# PowerBoard_Rev1.net
KiCad netlist of a schematic drawn in Altium Designer
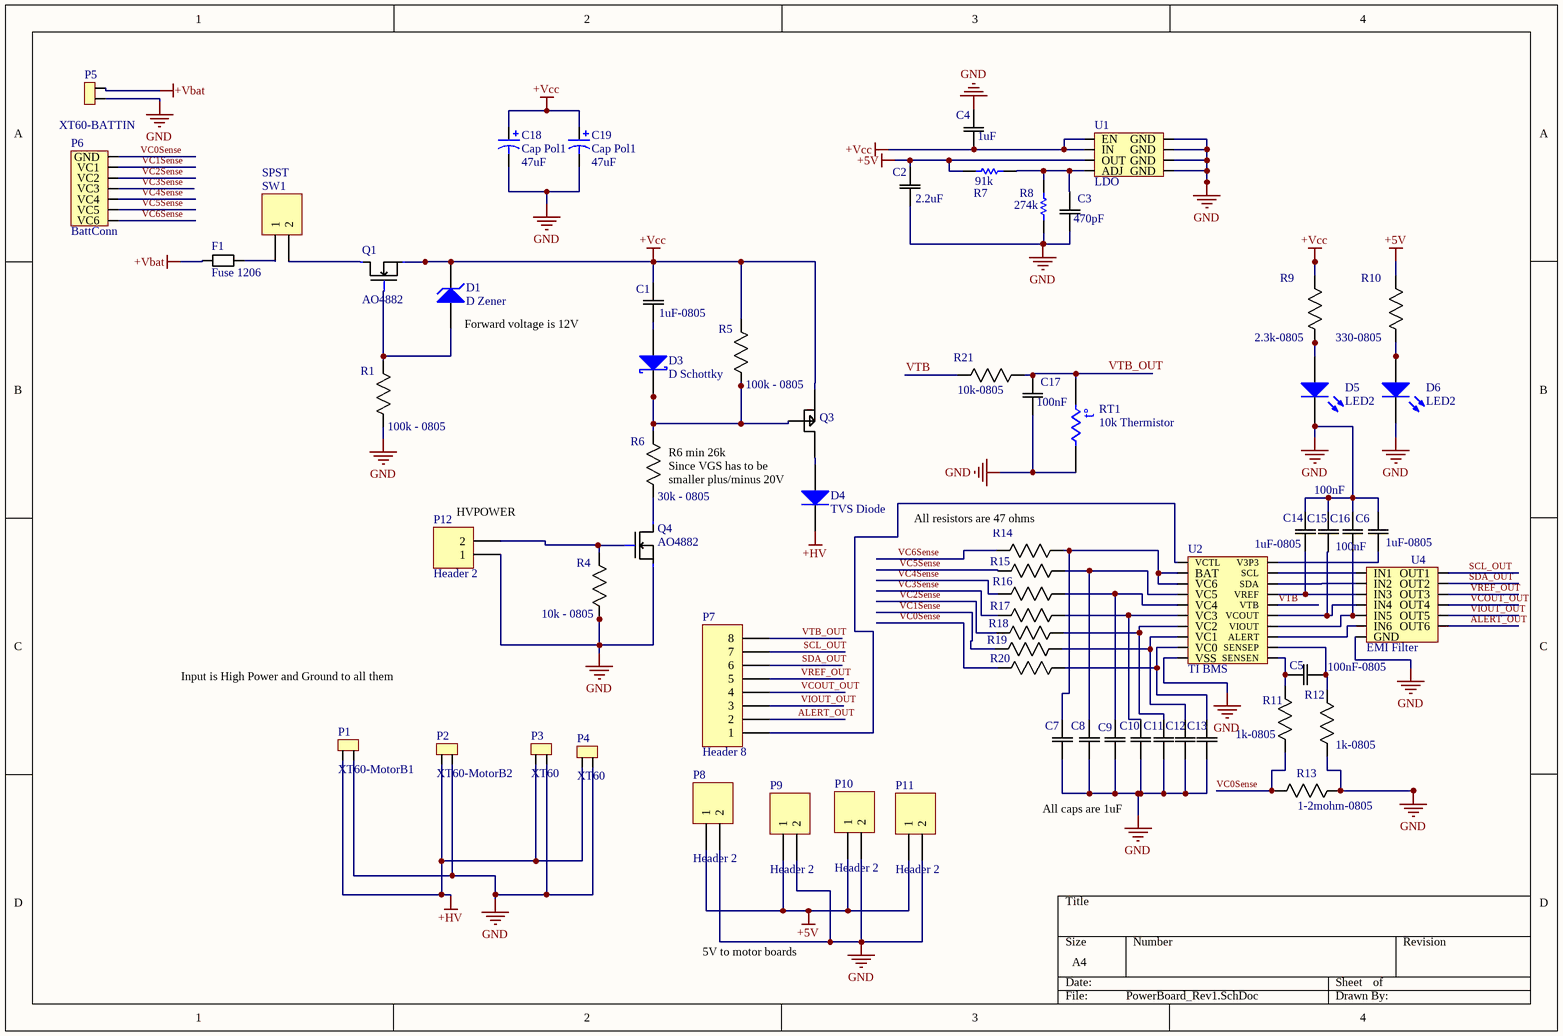
[diagram p0: PowerBoard_Rev1.SchDoc]

(export (version "E")
  (design (tool "Eeschema 10.0.6"))
  (components
    (comp (ref "C1")
      (value "1uF-0805")
      (footprint "CAPC2013X110N")
      (description "Capacitor; Ceramic; Cap; .100UF ; Tol+-10%; SMD; Vol-Rtg 50V; X7R, Tape/Reel")
      (fields (field (name "MP") "C0805C104K5RACTU") (field (name "MF") "Kemet"))
      (libsource (lib "100nF-C0805C104K5RACTU") (part "C0805C104K5RACTU"))
    )
    (comp (ref "C2")
      (value "2.2uF")
      (footprint "CAPC2013X110N")
      (description "Capacitor; Ceramic; Cap; .100UF ; Tol+-10%; SMD; Vol-Rtg 50V; X7R, Tape/Reel")
      (fields (field (name "MP") "C0805C104K5RACTU") (field (name "MF") "Kemet"))
      (libsource (lib "") (part "C0805C104K5RACTU_1"))
    )
    (comp (ref "C3")
      (value "470pF")
      (footprint "CAPC2013X110N")
      (description "Capacitor; Ceramic; Cap; .100UF ; Tol+-10%; SMD; Vol-Rtg 50V; X7R, Tape/Reel")
      (fields (field (name "MP") "C0805C104K5RACTU") (field (name "MF") "Kemet"))
      (libsource (lib "") (part "C0805C104K5RACTU_1"))
    )
    (comp (ref "C4")
      (value "1uF")
      (footprint "CAPC2013X110N")
      (description "Capacitor; Ceramic; Cap; .100UF ; Tol+-10%; SMD; Vol-Rtg 50V; X7R, Tape/Reel")
      (fields (field (name "MP") "C0805C104K5RACTU") (field (name "MF") "Kemet"))
      (libsource (lib "") (part "C0805C104K5RACTU_1"))
    )
    (comp (ref "C5")
      (value "100nF-0805")
      (footprint "CAPC2013X110N")
      (description "Capacitor; Ceramic; Cap; .100UF ; Tol+-10%; SMD; Vol-Rtg 50V; X7R, Tape/Reel")
      (fields (field (name "MP") "C0805C104K5RACTU") (field (name "MF") "Kemet"))
      (libsource (lib "100nF-C0805C104K5RACTU") (part "C0805C104K5RACTU"))
    )
    (comp (ref "C6")
      (value "1uF-0805")
      (footprint "CAPC2013X110N")
      (description "Capacitor; Ceramic; Cap; .100UF ; Tol+-10%; SMD; Vol-Rtg 50V; X7R, Tape/Reel")
      (fields (field (name "MP") "C0805C104K5RACTU") (field (name "MF") "Kemet"))
      (libsource (lib "100nF-C0805C104K5RACTU") (part "C0805C104K5RACTU"))
    )
    (comp (ref "C7")
      (value "1uF-0805")
      (footprint "CAPC2013X110N")
      (description "Capacitor; Ceramic; Cap; .100UF ; Tol+-10%; SMD; Vol-Rtg 50V; X7R, Tape/Reel")
      (fields (field (name "MP") "C0805C104K5RACTU") (field (name "MF") "Kemet"))
      (libsource (lib "100nF-C0805C104K5RACTU") (part "C0805C104K5RACTU"))
    )
    (comp (ref "C8")
      (value "1uF-0805")
      (footprint "CAPC2013X110N")
      (description "Capacitor; Ceramic; Cap; .100UF ; Tol+-10%; SMD; Vol-Rtg 50V; X7R, Tape/Reel")
      (fields (field (name "MP") "C0805C104K5RACTU") (field (name "MF") "Kemet"))
      (libsource (lib "100nF-C0805C104K5RACTU") (part "C0805C104K5RACTU"))
    )
    (comp (ref "C9")
      (value "1uF-0805")
      (footprint "CAPC2013X110N")
      (description "Capacitor; Ceramic; Cap; .100UF ; Tol+-10%; SMD; Vol-Rtg 50V; X7R, Tape/Reel")
      (fields (field (name "MP") "C0805C104K5RACTU") (field (name "MF") "Kemet"))
      (libsource (lib "100nF-C0805C104K5RACTU") (part "C0805C104K5RACTU"))
    )
    (comp (ref "C10")
      (value "1uF-0805")
      (footprint "CAPC2013X110N")
      (description "Capacitor; Ceramic; Cap; .100UF ; Tol+-10%; SMD; Vol-Rtg 50V; X7R, Tape/Reel")
      (fields (field (name "MP") "C0805C104K5RACTU") (field (name "MF") "Kemet"))
      (libsource (lib "100nF-C0805C104K5RACTU") (part "C0805C104K5RACTU"))
    )
    (comp (ref "C11")
      (value "1uF-0805")
      (footprint "CAPC2013X110N")
      (description "Capacitor; Ceramic; Cap; .100UF ; Tol+-10%; SMD; Vol-Rtg 50V; X7R, Tape/Reel")
      (fields (field (name "MP") "C0805C104K5RACTU") (field (name "MF") "Kemet"))
      (libsource (lib "100nF-C0805C104K5RACTU") (part "C0805C104K5RACTU"))
    )
    (comp (ref "C12")
      (value "1uF-0805")
      (footprint "CAPC2013X110N")
      (description "Capacitor; Ceramic; Cap; .100UF ; Tol+-10%; SMD; Vol-Rtg 50V; X7R, Tape/Reel")
      (fields (field (name "MP") "C0805C104K5RACTU") (field (name "MF") "Kemet"))
      (libsource (lib "100nF-C0805C104K5RACTU") (part "C0805C104K5RACTU"))
    )
    (comp (ref "C13")
      (value "1uF-0805")
      (footprint "CAPC2013X110N")
      (description "Capacitor; Ceramic; Cap; .100UF ; Tol+-10%; SMD; Vol-Rtg 50V; X7R, Tape/Reel")
      (fields (field (name "MP") "C0805C104K5RACTU") (field (name "MF") "Kemet"))
      (libsource (lib "100nF-C0805C104K5RACTU") (part "C0805C104K5RACTU"))
    )
    (comp (ref "C14")
      (value "1uF-0805")
      (footprint "CAPC2013X110N")
      (description "Capacitor; Ceramic; Cap; .100UF ; Tol+-10%; SMD; Vol-Rtg 50V; X7R, Tape/Reel")
      (fields (field (name "MP") "C0805C104K5RACTU") (field (name "MF") "Kemet"))
      (libsource (lib "100nF-C0805C104K5RACTU") (part "C0805C104K5RACTU"))
    )
    (comp (ref "C15")
      (value "100nF")
      (footprint "CAPC2013X110N")
      (description "Capacitor; Ceramic; Cap; .100UF ; Tol+-10%; SMD; Vol-Rtg 50V; X7R, Tape/Reel")
      (fields (field (name "MP") "C0805C104K5RACTU") (field (name "MF") "Kemet"))
      (libsource (lib "100nF-C0805C104K5RACTU") (part "C0805C104K5RACTU"))
    )
    (comp (ref "C16")
      (value "100nF")
      (footprint "CAPC2013X110N")
      (description "Capacitor; Ceramic; Cap; .100UF ; Tol+-10%; SMD; Vol-Rtg 50V; X7R, Tape/Reel")
      (fields (field (name "MP") "C0805C104K5RACTU") (field (name "MF") "Kemet"))
      (libsource (lib "100nF-C0805C104K5RACTU") (part "C0805C104K5RACTU"))
    )
    (comp (ref "C17")
      (value "100nF")
      (footprint "CAPC2013X110N")
      (description "Capacitor; Ceramic; Cap; .100UF ; Tol+-10%; SMD; Vol-Rtg 50V; X7R, Tape/Reel")
      (fields (field (name "MP") "C0805C104K5RACTU") (field (name "MF") "Kemet"))
      (libsource (lib "100nF-C0805C104K5RACTU") (part "C0805C104K5RACTU"))
    )
    (comp (ref "C18")
      (value "Cap Pol1")
      (footprint "RB7.6-15")
      (description "Polarized Capacitor (Radial)")
      (fields (field (name "ALTIUM_VALUE") "47uF") (field (name "PUBLISHER") "Altium Limited"))
      (libsource (lib "Miscellaneous Devices") (part "Cap Pol1"))
    )
    (comp (ref "C19")
      (value "Cap Pol1")
      (footprint "RB7.6-15")
      (description "Polarized Capacitor (Radial)")
      (fields (field (name "ALTIUM_VALUE") "47uF") (field (name "PUBLISHER") "Altium Limited"))
      (libsource (lib "Miscellaneous Devices") (part "Cap Pol1"))
    )
    (comp (ref "D1")
      (value "D Zener")
      (footprint "DIODE-0.7")
      (description "Zener Diode")
      (fields (field (name "PUBLISHER") "Altium Limited"))
      (libsource (lib "Miscellaneous Devices") (part "D Zener"))
    )
    (comp (ref "D3")
      (value "D Schottky")
      (footprint "SMB")
      (description "Schottky Diode")
      (fields (field (name "PUBLISHER") "Altium Limited"))
      (libsource (lib "Miscellaneous Devices") (part "D Schottky"))
    )
    (comp (ref "D4")
      (value "TVS Diode")
      (footprint "DO-35")
      (description "High Conductance Fast Diode")
      (fields (field (name "PUBLISHER") "Altium Limited"))
      (libsource (lib "Miscellaneous Devices") (part "Diode 1N914"))
    )
    (comp (ref "D5")
      (value "LED2")
      (footprint "3.2X1.6X1.1")
      (description "Typical RED, GREEN, YELLOW, AMBER GaAs LED")
      (fields (field (name "PUBLISHER") "Altium Limited"))
      (libsource (lib "Miscellaneous Devices") (part "LED2"))
    )
    (comp (ref "D6")
      (value "LED2")
      (footprint "3.2X1.6X1.1")
      (description "Typical RED, GREEN, YELLOW, AMBER GaAs LED")
      (fields (field (name "PUBLISHER") "Altium Limited"))
      (libsource (lib "Miscellaneous Devices") (part "LED2"))
    )
    (comp (ref "F1")
      (value "Fuse 1206")
      (footprint "PCBComponent_1")
      (libsource (lib "fuse_1206") (part "F?"))
    )
    (comp (ref "P1")
      (value "XT60-MotorB1")
      (footprint "PCBComponent_1")
      (libsource (lib "XT60") (part "Component_1"))
    )
    (comp (ref "P2")
      (value "XT60-MotorB2")
      (footprint "PCBComponent_1")
      (libsource (lib "XT60") (part "Component_1"))
    )
    (comp (ref "P3")
      (value "XT60")
      (footprint "PCBComponent_1")
      (libsource (lib "XT60") (part "Component_1"))
    )
    (comp (ref "P4")
      (value "XT60")
      (footprint "PCBComponent_1")
      (libsource (lib "XT60") (part "Component_1"))
    )
    (comp (ref "P5")
      (value "XT60-BATTIN")
      (footprint "PCBComponent_1")
      (libsource (lib "") (part "Component_1_1"))
    )
    (comp (ref "P6")
      (value "BattConn")
      (footprint "6sBattConn")
      (libsource (lib "455-2271-ND-Batt-Conn") (part "Component_1"))
    )
    (comp (ref "P7")
      (value "Header 8")
      (footprint "HDR1X8")
      (description "Header, 8-Pin")
      (fields (field (name "PUBLISHER") "Altium Limited"))
      (libsource (lib "Miscellaneous Connectors") (part "Header 8"))
    )
    (comp (ref "P8")
      (value "Header 2")
      (footprint "HDR1X2")
      (description "Header, 2-Pin")
      (fields (field (name "PUBLISHER") "Altium Limited"))
      (libsource (lib "Miscellaneous Connectors") (part "Header 2"))
    )
    (comp (ref "P9")
      (value "Header 2")
      (footprint "HDR1X2")
      (description "Header, 2-Pin")
      (fields (field (name "PUBLISHER") "Altium Limited"))
      (libsource (lib "Miscellaneous Connectors") (part "Header 2"))
    )
    (comp (ref "P10")
      (value "Header 2")
      (footprint "HDR1X2")
      (description "Header, 2-Pin")
      (fields (field (name "PUBLISHER") "Altium Limited"))
      (libsource (lib "Miscellaneous Connectors") (part "Header 2"))
    )
    (comp (ref "P11")
      (value "Header 2")
      (footprint "HDR1X2")
      (description "Header, 2-Pin")
      (fields (field (name "PUBLISHER") "Altium Limited"))
      (libsource (lib "Miscellaneous Connectors") (part "Header 2"))
    )
    (comp (ref "P12")
      (value "Header 2")
      (footprint "HDR1X2")
      (description "Header, 2-Pin")
      (fields (field (name "PUBLISHER") "Altium Limited"))
      (libsource (lib "") (part "Header 2_1"))
    )
    (comp (ref "Q1")
      (value "AO4882")
      (footprint "SOIC127P600X170-8N")
      (libsource (lib "AO4882") (part "Component_1"))
    )
    (comp (ref "Q3")
      (value "Mosfet P Channel")
      (footprint "SOIC127P600X170-8N")
      (libsource (lib "SI4497DY-T1-GE3CT-ND") (part "Q?"))
    )
    (comp (ref "Q4")
      (value "AO4882")
      (footprint "SOIC127P600X170-8N")
      (libsource (lib "AO4882") (part "Component_1"))
    )
    (comp (ref "R1")
      (value "100k - 0805")
      (footprint "RESC2013X65N")
      (description "Res Thick Film 0805 2.2K Ohm 1% 0.125W_1/8W_ Â}100ppm/ÂÂŽ Molded SMD Paper T/R")
      (fields (field (name "MP") "RC0805FR-072K2L") (field (name "MF") "Yageo"))
      (libsource (lib "RC0805FR-072K2L") (part "RC0805FR-072K2L"))
    )
    (comp (ref "R4")
      (value "10k - 0805")
      (footprint "RESC2013X65N")
      (description "Res Thick Film 0805 2.2K Ohm 1% 0.125W_1/8W_ Â}100ppm/ÂÂŽ Molded SMD Paper T/R")
      (fields (field (name "MP") "RC0805FR-072K2L") (field (name "MF") "Yageo"))
      (libsource (lib "RC0805FR-072K2L") (part "RC0805FR-072K2L"))
    )
    (comp (ref "R5")
      (value "100k - 0805")
      (footprint "RESC2013X65N")
      (description "Res Thick Film 0805 2.2K Ohm 1% 0.125W_1/8W_ Â}100ppm/ÂÂŽ Molded SMD Paper T/R")
      (fields (field (name "MP") "RC0805FR-072K2L") (field (name "MF") "Yageo"))
      (libsource (lib "") (part "RC0805FR-072K2L_1"))
    )
    (comp (ref "R6")
      (value "30k - 0805")
      (footprint "RESC2013X65N")
      (description "Res Thick Film 0805 2.2K Ohm 1% 0.125W_1/8W_ Â}100ppm/ÂÂŽ Molded SMD Paper T/R")
      (fields (field (name "MP") "RC0805FR-072K2L") (field (name "MF") "Yageo"))
      (libsource (lib "") (part "RC0805FR-072K2L_1"))
    )
    (comp (ref "R7")
      (value "91k")
      (footprint "AXIAL-0.3")
      (description "Resistor")
      (fields (field (name "PUBLISHER") "Altium Limited"))
      (libsource (lib "Miscellaneous Devices") (part "Res1"))
    )
    (comp (ref "R8")
      (value "274k")
      (footprint "AXIAL-0.3")
      (description "Resistor")
      (fields (field (name "PUBLISHER") "Altium Limited"))
      (libsource (lib "Miscellaneous Devices") (part "Res1"))
    )
    (comp (ref "R9")
      (value "2.3k-0805")
      (footprint "RESC2013X65N")
      (description "Res Thick Film 0805 2.2K Ohm 1% 0.125W_1/8W_ Â}100ppm/ÂÂŽ Molded SMD Paper T/R")
      (fields (field (name "MP") "RC0805FR-072K2L") (field (name "MF") "Yageo"))
      (libsource (lib "") (part "RC0805FR-072K2L_1"))
    )
    (comp (ref "R10")
      (value "330-0805")
      (footprint "RESC2013X65N")
      (description "Res Thick Film 0805 2.2K Ohm 1% 0.125W_1/8W_ Â}100ppm/ÂÂŽ Molded SMD Paper T/R")
      (fields (field (name "MP") "RC0805FR-072K2L") (field (name "MF") "Yageo"))
      (libsource (lib "RC0805FR-072K2L") (part "RC0805FR-072K2L"))
    )
    (comp (ref "R11")
      (value "1k-0805")
      (footprint "RESC2013X65N")
      (description "Res Thick Film 0805 2.2K Ohm 1% 0.125W_1/8W_ Â}100ppm/ÂÂŽ Molded SMD Paper T/R")
      (fields (field (name "MP") "RC0805FR-072K2L") (field (name "MF") "Yageo"))
      (libsource (lib "RC0805FR-072K2L") (part "RC0805FR-072K2L"))
    )
    (comp (ref "R12")
      (value "1k-0805")
      (footprint "RESC2013X65N")
      (description "Res Thick Film 0805 2.2K Ohm 1% 0.125W_1/8W_ Â}100ppm/ÂÂŽ Molded SMD Paper T/R")
      (fields (field (name "MP") "RC0805FR-072K2L") (field (name "MF") "Yageo"))
      (libsource (lib "RC0805FR-072K2L") (part "RC0805FR-072K2L"))
    )
    (comp (ref "R13")
      (value "1-2mohm-0805")
      (footprint "RESC2013X65N")
      (description "Res Thick Film 0805 2.2K Ohm 1% 0.125W_1/8W_ Â}100ppm/ÂÂŽ Molded SMD Paper T/R")
      (fields (field (name "MP") "RC0805FR-072K2L") (field (name "MF") "Yageo"))
      (libsource (lib "RC0805FR-072K2L") (part "RC0805FR-072K2L"))
    )
    (comp (ref "R14")
      (value "47-0805")
      (footprint "RESC2013X65N")
      (description "Res Thick Film 0805 2.2K Ohm 1% 0.125W_1/8W_ Â}100ppm/ÂÂŽ Molded SMD Paper T/R")
      (fields (field (name "MP") "RC0805FR-072K2L") (field (name "MF") "Yageo"))
      (libsource (lib "") (part "RC0805FR-072K2L_1"))
    )
    (comp (ref "R15")
      (value "47-0805")
      (footprint "RESC2013X65N")
      (description "Res Thick Film 0805 2.2K Ohm 1% 0.125W_1/8W_ Â}100ppm/ÂÂŽ Molded SMD Paper T/R")
      (fields (field (name "MP") "RC0805FR-072K2L") (field (name "MF") "Yageo"))
      (libsource (lib "") (part "RC0805FR-072K2L_1"))
    )
    (comp (ref "R16")
      (value "47-0805")
      (footprint "RESC2013X65N")
      (description "Res Thick Film 0805 2.2K Ohm 1% 0.125W_1/8W_ Â}100ppm/ÂÂŽ Molded SMD Paper T/R")
      (fields (field (name "MP") "RC0805FR-072K2L") (field (name "MF") "Yageo"))
      (libsource (lib "RC0805FR-072K2L") (part "RC0805FR-072K2L"))
    )
    (comp (ref "R17")
      (value "47-0805")
      (footprint "RESC2013X65N")
      (description "Res Thick Film 0805 2.2K Ohm 1% 0.125W_1/8W_ Â}100ppm/ÂÂŽ Molded SMD Paper T/R")
      (fields (field (name "MP") "RC0805FR-072K2L") (field (name "MF") "Yageo"))
      (libsource (lib "RC0805FR-072K2L") (part "RC0805FR-072K2L"))
    )
    (comp (ref "R18")
      (value "47-0805")
      (footprint "RESC2013X65N")
      (description "Res Thick Film 0805 2.2K Ohm 1% 0.125W_1/8W_ Â}100ppm/ÂÂŽ Molded SMD Paper T/R")
      (fields (field (name "MP") "RC0805FR-072K2L") (field (name "MF") "Yageo"))
      (libsource (lib "RC0805FR-072K2L") (part "RC0805FR-072K2L"))
    )
    (comp (ref "R19")
      (value "47-0805")
      (footprint "RESC2013X65N")
      (description "Res Thick Film 0805 2.2K Ohm 1% 0.125W_1/8W_ Â}100ppm/ÂÂŽ Molded SMD Paper T/R")
      (fields (field (name "MP") "RC0805FR-072K2L") (field (name "MF") "Yageo"))
      (libsource (lib "") (part "RC0805FR-072K2L_1"))
    )
    (comp (ref "R20")
      (value "47-0805")
      (footprint "RESC2013X65N")
      (description "Res Thick Film 0805 2.2K Ohm 1% 0.125W_1/8W_ Â}100ppm/ÂÂŽ Molded SMD Paper T/R")
      (fields (field (name "MP") "RC0805FR-072K2L") (field (name "MF") "Yageo"))
      (libsource (lib "RC0805FR-072K2L") (part "RC0805FR-072K2L"))
    )
    (comp (ref "R21")
      (value "10k-0805")
      (footprint "RESC2013X65N")
      (description "Res Thick Film 0805 2.2K Ohm 1% 0.125W_1/8W_ Â}100ppm/ÂÂŽ Molded SMD Paper T/R")
      (fields (field (name "MP") "RC0805FR-072K2L") (field (name "MF") "Yageo"))
      (libsource (lib "RC0805FR-072K2L") (part "RC0805FR-072K2L"))
    )
    (comp (ref "RT1")
      (value "10k Thermistor")
      (footprint "6-0805_N")
      (description "490-2456-1-ND")
      (fields (field (name "PUBLISHER") "Altium Limited"))
      (libsource (lib "Miscellaneous Devices") (part "Res Thermal"))
    )
    (comp (ref "SW1")
      (value "SPST")
      (footprint "HDR1X2")
      (description "SPST Switch")
      (fields (field (name "PUBLISHER") "Altium Limited"))
      (libsource (lib "Miscellaneous Connectors") (part "Header 2"))
    )
    (comp (ref "U1")
      (value "LDO")
      (footprint "SOIC127P600X170-8N")
      (libsource (lib "296-21569-1-ND") (part "U?"))
    )
    (comp (ref "U2")
      (value "TI BMS")
      (footprint "TSOP65P640X120-20N")
      (libsource (lib "296-29506-5-ND") (part "U?"))
    )
    (comp (ref "U4")
      (value "EMI Filter")
      (footprint "Filter")
      (libsource (lib "497-7740-1-ND") (part "EMIFilter"))
    )
  )
  (nets
    (net (code "1") (name "+5V") (class "Default")
      (node (ref "C2") (pin "2") (pinfunction "C2_2") (pintype "passive"))
      (node (ref "P10") (pin "1") (pinfunction "1_1") (pintype "passive"))
      (node (ref "P11") (pin "1") (pinfunction "1_1") (pintype "passive"))
      (node (ref "P8") (pin "1") (pinfunction "1_1") (pintype "passive"))
      (node (ref "P9") (pin "1") (pinfunction "1_1") (pintype "passive"))
      (node (ref "R10") (pin "2") (pinfunction "R2_2") (pintype "passive"))
      (node (ref "R7") (pin "1") (pinfunction "1_1") (pintype "passive"))
      (node (ref "U1") (pin "OUT") (pinfunction "OUT_OUT") (pintype "passive"))
    )
    (net (code "2") (name "+HV") (class "Default")
      (node (ref "D4") (pin "2") (pinfunction "K_2") (pintype "passive"))
      (node (ref "P1") (pin "1") (pinfunction "1_1") (pintype "passive"))
      (node (ref "P2") (pin "1") (pinfunction "1_1") (pintype "passive"))
      (node (ref "P3") (pin "1") (pinfunction "1_1") (pintype "passive"))
      (node (ref "P4") (pin "1") (pinfunction "1_1") (pintype "passive"))
    )
    (net (code "3") (name "+Vbat") (class "Default")
      (node (ref "F1") (pin "1") (pinfunction "1_1") (pintype "passive"))
      (node (ref "P5") (pin "2") (pinfunction "2_2") (pintype "passive"))
    )
    (net (code "4") (name "+Vcc") (class "Default")
      (node (ref "C1") (pin "2") (pinfunction "C2_2") (pintype "passive"))
      (node (ref "C18") (pin "1") (pinfunction "1_1") (pintype "passive"))
      (node (ref "C19") (pin "1") (pinfunction "1_1") (pintype "passive"))
      (node (ref "C4") (pin "1") (pinfunction "C1_1") (pintype "passive"))
      (node (ref "D1") (pin "2") (pinfunction "K_2") (pintype "passive"))
      (node (ref "Q1") (pin "S") (pinfunction "S_S") (pintype "passive"))
      (node (ref "Q3") (pin "S") (pinfunction "S_S") (pintype "passive"))
      (node (ref "R5") (pin "1") (pinfunction "R1_1") (pintype "passive"))
      (node (ref "R9") (pin "2") (pinfunction "R2_2") (pintype "passive"))
      (node (ref "U1") (pin "EN") (pinfunction "EN_EN") (pintype "passive"))
      (node (ref "U1") (pin "IN") (pinfunction "IN_IN") (pintype "passive"))
    )
    (net (code "6") (name "/ALERT_OUT") (class "Default")
      (node (ref "P7") (pin "2") (pinfunction "2_2") (pintype "passive"))
      (node (ref "U4") (pin "12") (pinfunction "OUT6_12") (pintype "passive"))
    )
    (net (code "7") (name "/SCL_OUT") (class "Default")
      (node (ref "P7") (pin "7") (pinfunction "7_7") (pintype "passive"))
      (node (ref "U4") (pin "7") (pinfunction "OUT1_7") (pintype "passive"))
    )
    (net (code "8") (name "/SDA_OUT") (class "Default")
      (node (ref "P7") (pin "6") (pinfunction "6_6") (pintype "passive"))
      (node (ref "U4") (pin "8") (pinfunction "OUT2_8") (pintype "passive"))
    )
    (net (code "9") (name "/VC0Sense") (class "Default")
      (node (ref "P6") (pin "GND") (pinfunction "GND_GND") (pintype "passive"))
      (node (ref "R11") (pin "2") (pinfunction "R2_2") (pintype "passive"))
      (node (ref "R13") (pin "1") (pinfunction "R1_1") (pintype "passive"))
      (node (ref "R20") (pin "1") (pinfunction "R1_1") (pintype "passive"))
    )
    (net (code "10") (name "/VC1Sense") (class "Default")
      (node (ref "P6") (pin "VC1") (pinfunction "VC1_VC1") (pintype "passive"))
      (node (ref "R19") (pin "1") (pinfunction "R1_1") (pintype "passive"))
    )
    (net (code "11") (name "/VC2Sense") (class "Default")
      (node (ref "P6") (pin "VC2") (pinfunction "VC2_VC2") (pintype "passive"))
      (node (ref "R18") (pin "1") (pinfunction "R1_1") (pintype "passive"))
    )
    (net (code "12") (name "/VC3Sense") (class "Default")
      (node (ref "P6") (pin "VC3") (pinfunction "VC3_VC3") (pintype "passive"))
      (node (ref "R17") (pin "1") (pinfunction "R1_1") (pintype "passive"))
    )
    (net (code "13") (name "/VC4Sense") (class "Default")
      (node (ref "P6") (pin "VC4") (pinfunction "VC4_VC4") (pintype "passive"))
      (node (ref "R16") (pin "1") (pinfunction "R1_1") (pintype "passive"))
    )
    (net (code "14") (name "/VC5Sense") (class "Default")
      (node (ref "P6") (pin "VC5") (pinfunction "VC5_VC5") (pintype "passive"))
      (node (ref "R15") (pin "1") (pinfunction "R1_1") (pintype "passive"))
    )
    (net (code "15") (name "/VC6Sense") (class "Default")
      (node (ref "P6") (pin "VC6") (pinfunction "VC6_VC6") (pintype "passive"))
      (node (ref "R14") (pin "1") (pinfunction "R1_1") (pintype "passive"))
    )
    (net (code "16") (name "/VCOUT_OUT") (class "Default")
      (node (ref "P7") (pin "4") (pinfunction "4_4") (pintype "passive"))
      (node (ref "U4") (pin "10") (pinfunction "OUT4_10") (pintype "passive"))
    )
    (net (code "17") (name "/VIOUT_OUT") (class "Default")
      (node (ref "P7") (pin "3") (pinfunction "3_3") (pintype "passive"))
      (node (ref "U4") (pin "11") (pinfunction "OUT5_11") (pintype "passive"))
    )
    (net (code "18") (name "/VREF_OUT") (class "Default")
      (node (ref "P7") (pin "5") (pinfunction "5_5") (pintype "passive"))
      (node (ref "U4") (pin "9") (pinfunction "OUT3_9") (pintype "passive"))
    )
    (net (code "19") (name "/VTB") (class "Default")
      (node (ref "R21") (pin "1") (pinfunction "R1_1") (pintype "passive"))
      (node (ref "U2") (pin "VTB") (pinfunction "VTB_VTB") (pintype "passive"))
    )
    (net (code "20") (name "/VTB_OUT") (class "Default")
      (node (ref "C17") (pin "2") (pinfunction "C2_2") (pintype "passive"))
      (node (ref "P7") (pin "8") (pinfunction "8_8") (pintype "passive"))
      (node (ref "R21") (pin "2") (pinfunction "R2_2") (pintype "passive"))
      (node (ref "RT1") (pin "1") (pinfunction "1_1") (pintype "passive"))
    )
    (net (code "21") (name "GND") (class "Default")
      (node (ref "C10") (pin "1") (pinfunction "C1_1") (pintype "passive"))
      (node (ref "C11") (pin "1") (pinfunction "C1_1") (pintype "passive"))
      (node (ref "C12") (pin "1") (pinfunction "C1_1") (pintype "passive"))
      (node (ref "C13") (pin "1") (pinfunction "C1_1") (pintype "passive"))
      (node (ref "C14") (pin "2") (pinfunction "C2_2") (pintype "passive"))
      (node (ref "C15") (pin "2") (pinfunction "C2_2") (pintype "passive"))
      (node (ref "C16") (pin "2") (pinfunction "C2_2") (pintype "passive"))
      (node (ref "C17") (pin "1") (pinfunction "C1_1") (pintype "passive"))
      (node (ref "C18") (pin "2") (pinfunction "2_2") (pintype "passive"))
      (node (ref "C19") (pin "2") (pinfunction "2_2") (pintype "passive"))
      (node (ref "C2") (pin "1") (pinfunction "C1_1") (pintype "passive"))
      (node (ref "C3") (pin "1") (pinfunction "C1_1") (pintype "passive"))
      (node (ref "C4") (pin "2") (pinfunction "C2_2") (pintype "passive"))
      (node (ref "C6") (pin "2") (pinfunction "C2_2") (pintype "passive"))
      (node (ref "C7") (pin "1") (pinfunction "C1_1") (pintype "passive"))
      (node (ref "C8") (pin "1") (pinfunction "C1_1") (pintype "passive"))
      (node (ref "C9") (pin "1") (pinfunction "C1_1") (pintype "passive"))
      (node (ref "D5") (pin "2") (pinfunction "K_2") (pintype "passive"))
      (node (ref "D6") (pin "2") (pinfunction "K_2") (pintype "passive"))
      (node (ref "P1") (pin "2") (pinfunction "2_2") (pintype "passive"))
      (node (ref "P10") (pin "2") (pinfunction "2_2") (pintype "passive"))
      (node (ref "P11") (pin "2") (pinfunction "2_2") (pintype "passive"))
      (node (ref "P12") (pin "1") (pinfunction "1_1") (pintype "passive"))
      (node (ref "P2") (pin "2") (pinfunction "2_2") (pintype "passive"))
      (node (ref "P3") (pin "2") (pinfunction "2_2") (pintype "passive"))
      (node (ref "P4") (pin "2") (pinfunction "2_2") (pintype "passive"))
      (node (ref "P5") (pin "1") (pinfunction "1_1") (pintype "passive"))
      (node (ref "P8") (pin "2") (pinfunction "2_2") (pintype "passive"))
      (node (ref "P9") (pin "2") (pinfunction "2_2") (pintype "passive"))
      (node (ref "Q4") (pin "S") (pinfunction "S_S") (pintype "passive"))
      (node (ref "R1") (pin "2") (pinfunction "R2_2") (pintype "passive"))
      (node (ref "R12") (pin "2") (pinfunction "R2_2") (pintype "passive"))
      (node (ref "R13") (pin "2") (pinfunction "R2_2") (pintype "passive"))
      (node (ref "R4") (pin "2") (pinfunction "R2_2") (pintype "passive"))
      (node (ref "R8") (pin "2") (pinfunction "2_2") (pintype "passive"))
      (node (ref "RT1") (pin "2") (pinfunction "2_2") (pintype "passive"))
      (node (ref "U1") (pin "GND") (pinfunction "GND_GND") (pintype "passive"))
      (node (ref "U2") (pin "VSS") (pinfunction "VSS_VSS") (pintype "passive"))
      (node (ref "U4") (pin "GND") (pinfunction "GND_GND") (pintype "passive"))
    )
    (net (code "22") (name "Net-(C1-C1)") (class "Default")
      (node (ref "C1") (pin "1") (pinfunction "C1_1") (pintype "passive"))
      (node (ref "D3") (pin "1") (pinfunction "A_1") (pintype "passive"))
    )
    (net (code "23") (name "Net-(C3-C2)") (class "Default")
      (node (ref "C3") (pin "2") (pinfunction "C2_2") (pintype "passive"))
      (node (ref "R7") (pin "2") (pinfunction "2_2") (pintype "passive"))
      (node (ref "R8") (pin "1") (pinfunction "1_1") (pintype "passive"))
      (node (ref "U1") (pin "ADJ/BYP") (pinfunction "ADJ_ADJ/BYP") (pintype "passive"))
    )
    (net (code "24") (name "Net-(C5-C1)") (class "Default")
      (node (ref "C5") (pin "1") (pinfunction "C1_1") (pintype "passive"))
      (node (ref "R11") (pin "1") (pinfunction "R1_1") (pintype "passive"))
      (node (ref "U2") (pin "SENSEN") (pinfunction "SENSEN_SENSEN") (pintype "passive"))
    )
    (net (code "25") (name "Net-(C5-C2)") (class "Default")
      (node (ref "C5") (pin "2") (pinfunction "C2_2") (pintype "passive"))
      (node (ref "R12") (pin "1") (pinfunction "R1_1") (pintype "passive"))
      (node (ref "U2") (pin "SENSEP") (pinfunction "SENSEP_SENSEP") (pintype "passive"))
    )
    (net (code "26") (name "Net-(C6-C1)") (class "Default")
      (node (ref "C6") (pin "1") (pinfunction "C1_1") (pintype "passive"))
      (node (ref "U2") (pin "V3P3") (pinfunction "V3P3_V3P3") (pintype "passive"))
    )
    (net (code "27") (name "Net-(C7-C2)") (class "Default")
      (node (ref "C7") (pin "2") (pinfunction "C2_2") (pintype "passive"))
      (node (ref "R14") (pin "2") (pinfunction "R2_2") (pintype "passive"))
      (node (ref "U2") (pin "BAT") (pinfunction "BAT_BAT") (pintype "passive"))
      (node (ref "U2") (pin "VC6") (pinfunction "VC6_VC6") (pintype "passive"))
    )
    (net (code "28") (name "Net-(C8-C2)") (class "Default")
      (node (ref "C8") (pin "2") (pinfunction "C2_2") (pintype "passive"))
      (node (ref "R15") (pin "2") (pinfunction "R2_2") (pintype "passive"))
      (node (ref "U2") (pin "VC5") (pinfunction "VC5_VC5") (pintype "passive"))
    )
    (net (code "29") (name "Net-(C9-C2)") (class "Default")
      (node (ref "C9") (pin "2") (pinfunction "C2_2") (pintype "passive"))
      (node (ref "R16") (pin "2") (pinfunction "R2_2") (pintype "passive"))
      (node (ref "U2") (pin "VC4") (pinfunction "VC4_VC4") (pintype "passive"))
    )
    (net (code "30") (name "Net-(C10-C2)") (class "Default")
      (node (ref "C10") (pin "2") (pinfunction "C2_2") (pintype "passive"))
      (node (ref "R17") (pin "2") (pinfunction "R2_2") (pintype "passive"))
      (node (ref "U2") (pin "VC3") (pinfunction "VC3_VC3") (pintype "passive"))
    )
    (net (code "31") (name "Net-(C11-C2)") (class "Default")
      (node (ref "C11") (pin "2") (pinfunction "C2_2") (pintype "passive"))
      (node (ref "R18") (pin "2") (pinfunction "R2_2") (pintype "passive"))
      (node (ref "U2") (pin "VC2") (pinfunction "VC2_VC2") (pintype "passive"))
    )
    (net (code "32") (name "Net-(C12-C2)") (class "Default")
      (node (ref "C12") (pin "2") (pinfunction "C2_2") (pintype "passive"))
      (node (ref "R19") (pin "2") (pinfunction "R2_2") (pintype "passive"))
      (node (ref "U2") (pin "VC1") (pinfunction "VC1_VC1") (pintype "passive"))
    )
    (net (code "33") (name "Net-(C13-C2)") (class "Default")
      (node (ref "C13") (pin "2") (pinfunction "C2_2") (pintype "passive"))
      (node (ref "R20") (pin "2") (pinfunction "R2_2") (pintype "passive"))
      (node (ref "U2") (pin "VC0") (pinfunction "VC0_VC0") (pintype "passive"))
    )
    (net (code "34") (name "Net-(C14-C1)") (class "Default")
      (node (ref "C14") (pin "1") (pinfunction "C1_1") (pintype "passive"))
      (node (ref "U2") (pin "VREF") (pinfunction "VREF_VREF") (pintype "passive"))
      (node (ref "U4") (pin "3") (pinfunction "IN3_3") (pintype "passive"))
    )
    (net (code "35") (name "Net-(C15-C1)") (class "Default")
      (node (ref "C15") (pin "1") (pinfunction "C1_1") (pintype "passive"))
      (node (ref "U2") (pin "VCOUT") (pinfunction "VCOUT_VCOUT") (pintype "passive"))
      (node (ref "U4") (pin "4") (pinfunction "IN4_4") (pintype "passive"))
    )
    (net (code "36") (name "Net-(C16-C1)") (class "Default")
      (node (ref "C16") (pin "1") (pinfunction "C1_1") (pintype "passive"))
      (node (ref "U2") (pin "VIOUT") (pinfunction "VIOUT_VIOUT") (pintype "passive"))
      (node (ref "U4") (pin "5") (pinfunction "IN5_5") (pintype "passive"))
    )
    (net (code "37") (name "Net-(D1-A)") (class "Default")
      (node (ref "D1") (pin "1") (pinfunction "A_1") (pintype "passive"))
      (node (ref "Q1") (pin "G") (pinfunction "G_G") (pintype "passive"))
      (node (ref "R1") (pin "1") (pinfunction "R1_1") (pintype "passive"))
    )
    (net (code "38") (name "Net-(D3-K)") (class "Default")
      (node (ref "D3") (pin "2") (pinfunction "K_2") (pintype "passive"))
      (node (ref "Q3") (pin "G") (pinfunction "G_G") (pintype "passive"))
      (node (ref "R5") (pin "2") (pinfunction "R2_2") (pintype "passive"))
      (node (ref "R6") (pin "1") (pinfunction "R1_1") (pintype "passive"))
    )
    (net (code "39") (name "Net-(D4-A)") (class "Default")
      (node (ref "D4") (pin "1") (pinfunction "A_1") (pintype "passive"))
      (node (ref "Q3") (pin "D") (pinfunction "D_D") (pintype "passive"))
    )
    (net (code "40") (name "Net-(D5-A)") (class "Default")
      (node (ref "D5") (pin "1") (pinfunction "A_1") (pintype "passive"))
      (node (ref "R9") (pin "1") (pinfunction "R1_1") (pintype "passive"))
    )
    (net (code "41") (name "Net-(D6-A)") (class "Default")
      (node (ref "D6") (pin "1") (pinfunction "A_1") (pintype "passive"))
      (node (ref "R10") (pin "1") (pinfunction "R1_1") (pintype "passive"))
    )
    (net (code "42") (name "Net-(F1-Pad2)") (class "Default")
      (node (ref "F1") (pin "2") (pinfunction "2_2") (pintype "passive"))
      (node (ref "SW1") (pin "1") (pinfunction "1_1") (pintype "passive"))
    )
    (net (code "43") (name "Net-(P7-Pad1)") (class "Default")
      (node (ref "P7") (pin "1") (pinfunction "1_1") (pintype "passive"))
      (node (ref "U2") (pin "VCTL") (pinfunction "VCTL_VCTL") (pintype "passive"))
    )
    (net (code "44") (name "Net-(Q1-PadD)") (class "Default")
      (node (ref "Q1") (pin "D") (pinfunction "D_D") (pintype "passive"))
      (node (ref "SW1") (pin "2") (pinfunction "2_2") (pintype "passive"))
    )
    (net (code "45") (name "Net-(R4-R1)") (class "Default")
      (node (ref "P12") (pin "2") (pinfunction "2_2") (pintype "passive"))
      (node (ref "Q4") (pin "G") (pinfunction "G_G") (pintype "passive"))
      (node (ref "R4") (pin "1") (pinfunction "R1_1") (pintype "passive"))
    )
    (net (code "46") (name "Net-(R6-R2)") (class "Default")
      (node (ref "Q4") (pin "D") (pinfunction "D_D") (pintype "passive"))
      (node (ref "R6") (pin "2") (pinfunction "R2_2") (pintype "passive"))
    )
    (net (code "47") (name "Net-(U4-IN1)") (class "Default")
      (node (ref "U2") (pin "SCL") (pinfunction "SCL_SCL") (pintype "passive"))
      (node (ref "U4") (pin "1") (pinfunction "IN1_1") (pintype "passive"))
    )
    (net (code "48") (name "Net-(U4-IN2)") (class "Default")
      (node (ref "U2") (pin "SDA") (pinfunction "SDA_SDA") (pintype "passive"))
      (node (ref "U4") (pin "2") (pinfunction "IN2_2") (pintype "passive"))
    )
    (net (code "49") (name "Net-(U4-IN6)") (class "Default")
      (node (ref "U2") (pin "ALERT") (pinfunction "ALERT_ALERT") (pintype "passive"))
      (node (ref "U4") (pin "6") (pinfunction "IN6_6") (pintype "passive"))
    )
  )
)
